# pilote_poele_2020-12-16_14-18-25.net
KiCad netlist of a schematic drawn in EasyEDA
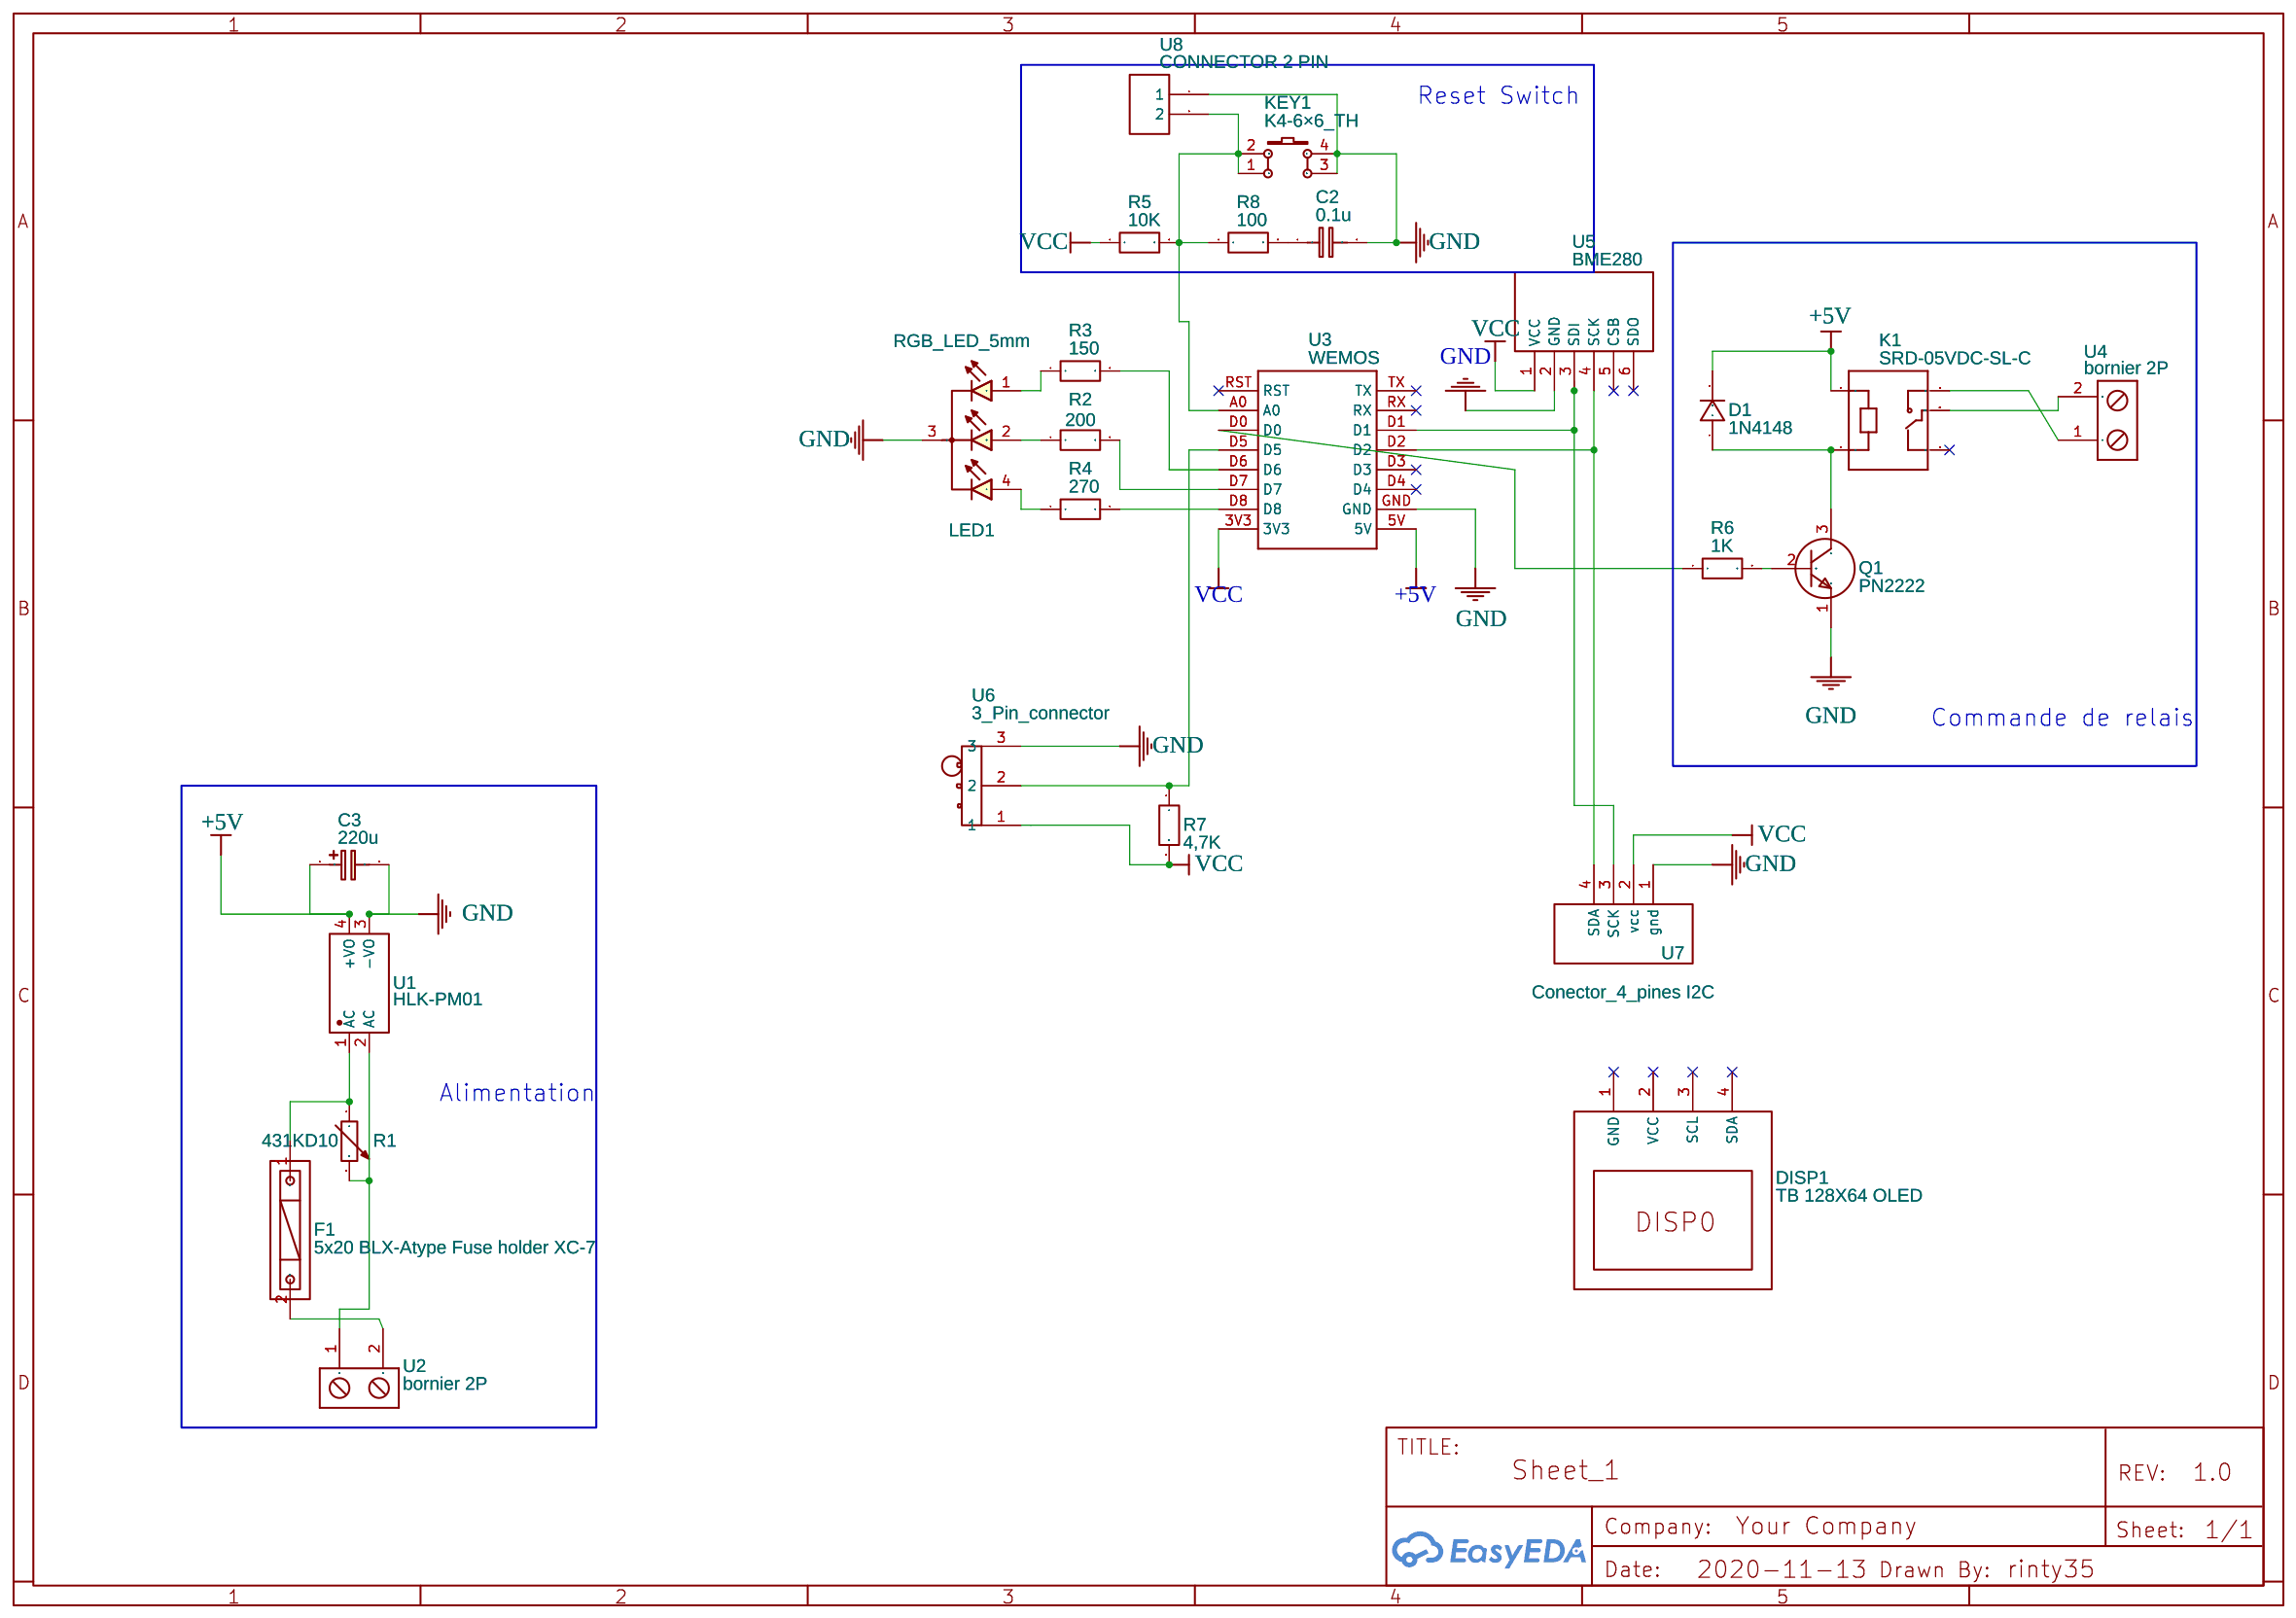
[diagram p0: schematic sheet]

(export (version "E")
  (design (tool "Eeschema 10.0.6"))
  (components
    (comp (ref "C2") (value "0.1u") (libsource (lib "") (part "C_0603_EU")))
    (comp (ref "C3") (value "220u") (libsource (lib "") (part "CE_TH_D4.0×F1.5_EU")))
    (comp (ref "D1")
      (value "1N4148")
      (fields (field (name "BOM_Supplier Part") "C14516"))
      (libsource (lib "") (part "1N4148"))
    )
    (comp (ref "DISP1") (value "TB 128X64 OLED") (libsource (lib "") (part "TB 128X64 OLED")))
    (comp (ref "F1")
      (value "5x20 BLX-Atype Fuse holder XC-7")
      (fields (field (name "BOM_Supplier Part") "C3131"))
      (libsource (lib "") (part "5x20 BLX-Atype Fuse holder XC-7"))
    )
    (comp (ref "K1") (value "SRD-05VDC-SL-C") (libsource (lib "") (part "SRD-05VDC-SL-C")))
    (comp (ref "KEY1")
      (value "K4-6×6_TH")
      (fields
        (field (name "BOM_Manufacturer Part") "K2-1102DP-E4SW-04")
        (field (name "BOM_Supplier Part") "C136684")
      )
      (libsource (lib "") (part "K4-6×6_TH"))
    )
    (comp (ref "LED1")
      (value "RGB_LED_5mm")
      (fields (field (name "BOM_Manufacturer Part") "φ5 RGB LED") (field (name "BOM_Supplier Part") "C32985"))
      (libsource (lib "") (part "RGB_LED_5mm"))
    )
    (comp (ref "Q1") (value "PN2222") (libsource (lib "") (part "PN2222")))
    (comp (ref "R1")
      (value "431KD10")
      (fields (field (name "BOM_Supplier Part") "C123332"))
      (libsource (lib "") (part "431KD10"))
    )
    (comp (ref "R2") (value "200") (libsource (lib "") (part "R_AXIAL-0.5_EU")))
    (comp (ref "R3") (value "150") (libsource (lib "") (part "R_AXIAL-0.5_EU")))
    (comp (ref "R4") (value "270") (libsource (lib "") (part "R_AXIAL-0.5_EU")))
    (comp (ref "R5") (value "10K") (libsource (lib "") (part "R_AXIAL-0.5_EU")))
    (comp (ref "R6") (value "1K") (libsource (lib "") (part "R_AXIAL-0.5_EU")))
    (comp (ref "R7") (value "4,7K") (libsource (lib "") (part "R_0603_EU")))
    (comp (ref "R8") (value "100") (libsource (lib "") (part "R_AXIAL-0.5_EU")))
    (comp (ref "U1")
      (value "HLK-PM01")
      (fields (field (name "BOM_Supplier Part") "C209903"))
      (libsource (lib "") (part "HLK-PM01"))
    )
    (comp (ref "U2")
      (value "bornier 2P")
      (fields (field (name "BOM_Manufacturer Part") "bornier"))
      (libsource (lib "") (part "bornier 2P_1"))
    )
    (comp (ref "U3") (value "WEMOS") (libsource (lib "") (part "WEMOS")))
    (comp (ref "U4")
      (value "bornier 2P")
      (fields (field (name "BOM_Manufacturer Part") "bornier"))
      (libsource (lib "") (part "bornier 2P"))
    )
    (comp (ref "U5") (value "BME280") (libsource (lib "") (part "BME280")))
    (comp (ref "U6")
      (value "3_Pin_connector")
      (fields (field (name "BOM_Manufacturer Part") "pin 3"))
      (libsource (lib "") (part "3_Pin_connector"))
    )
    (comp (ref "U7") (value "Conector_4_pines I2C") (libsource (lib "") (part "Conector_4_pines")))
    (comp (ref "U8") (value "CONNECTOR 2 PIN") (libsource (lib "") (part "CONNECTOR 2 PIN")))
  )
  (nets
    (net (code "1") (name "+5V") (class "Default")
      (node (ref "C3") (pin "1") (pinfunction "1_1") (pintype "unspecified"))
      (node (ref "D1") (pin "2") (pinfunction "2_2") (pintype "unspecified"))
      (node (ref "K1") (pin "A1") (pinfunction "A1_A1") (pintype "bidirectional"))
      (node (ref "U1") (pin "4") (pinfunction "+VO_4") (pintype "unspecified"))
      (node (ref "U3") (pin "5V") (pinfunction "5V_5V") (pintype "unspecified"))
    )
    (net (code "2") (name "GND") (class "Default")
      (node (ref "C2") (pin "2") (pinfunction "2_2") (pintype "unspecified"))
      (node (ref "C3") (pin "2") (pinfunction "2_2") (pintype "unspecified"))
      (node (ref "KEY1") (pin "3") (pinfunction "3_3") (pintype "unspecified"))
      (node (ref "KEY1") (pin "4") (pinfunction "4_4") (pintype "unspecified"))
      (node (ref "LED1") (pin "3") (pinfunction "3_3") (pintype "unspecified"))
      (node (ref "Q1") (pin "1") (pinfunction "E_1") (pintype "unspecified"))
      (node (ref "U1") (pin "3") (pinfunction "-VO_3") (pintype "unspecified"))
      (node (ref "U3") (pin "GND") (pinfunction "GND_GND") (pintype "unspecified"))
      (node (ref "U5") (pin "2") (pinfunction "GND_2") (pintype "unspecified"))
      (node (ref "U6") (pin "3") (pinfunction "3_3") (pintype "unspecified"))
      (node (ref "U7") (pin "1") (pinfunction "gnd_1") (pintype "unspecified"))
      (node (ref "U8") (pin "1") (pinfunction "1_1") (pintype "unspecified"))
    )
    (net (code "3") (name "Net-(C2-Pad1)") (class "Default")
      (node (ref "C2") (pin "1") (pinfunction "1_1") (pintype "unspecified"))
      (node (ref "R8") (pin "2") (pinfunction "2_2") (pintype "unspecified"))
    )
    (net (code "4") (name "Net-(F1-Pad1)") (class "Default")
      (node (ref "F1") (pin "1") (pinfunction "1_1") (pintype "unspecified"))
      (node (ref "R1") (pin "1") (pinfunction "1_1") (pintype "unspecified"))
      (node (ref "U1") (pin "1") (pinfunction "AC_1") (pintype "unspecified"))
    )
    (net (code "5") (name "Net-(F1-Pad2)") (class "Default")
      (node (ref "F1") (pin "2") (pinfunction "2_2") (pintype "unspecified"))
      (node (ref "U2") (pin "2") (pinfunction "2_2") (pintype "unspecified"))
    )
    (net (code "6") (name "Net-(K1-PadCOM)") (class "Default")
      (node (ref "K1") (pin "COM") (pinfunction "COM_COM") (pintype "bidirectional"))
      (node (ref "U4") (pin "2") (pinfunction "2_2") (pintype "unspecified"))
    )
    (net (code "7") (name "Net-(K1-PadNO)") (class "Default")
      (node (ref "K1") (pin "NO") (pinfunction "NO_NO") (pintype "bidirectional"))
      (node (ref "U4") (pin "1") (pinfunction "1_1") (pintype "unspecified"))
    )
    (net (code "8") (name "Net-(KEY1-Pad1)") (class "Default")
      (node (ref "KEY1") (pin "1") (pinfunction "1_1") (pintype "unspecified"))
      (node (ref "KEY1") (pin "2") (pinfunction "2_2") (pintype "unspecified"))
      (node (ref "R5") (pin "2") (pinfunction "2_2") (pintype "unspecified"))
      (node (ref "R8") (pin "1") (pinfunction "1_1") (pintype "unspecified"))
      (node (ref "U3") (pin "A0") (pinfunction "A0_A0") (pintype "unspecified"))
      (node (ref "U8") (pin "2") (pinfunction "2_2") (pintype "unspecified"))
    )
    (net (code "9") (name "Net-(LED1-Pad1)") (class "Default")
      (node (ref "LED1") (pin "1") (pinfunction "1_1") (pintype "unspecified"))
      (node (ref "R3") (pin "1") (pinfunction "1_1") (pintype "unspecified"))
    )
    (net (code "10") (name "Net-(LED1-Pad2)") (class "Default")
      (node (ref "LED1") (pin "2") (pinfunction "2_2") (pintype "unspecified"))
      (node (ref "R2") (pin "1") (pinfunction "1_1") (pintype "unspecified"))
    )
    (net (code "11") (name "Net-(LED1-Pad4)") (class "Default")
      (node (ref "LED1") (pin "4") (pinfunction "4_4") (pintype "unspecified"))
      (node (ref "R4") (pin "1") (pinfunction "1_1") (pintype "unspecified"))
    )
    (net (code "12") (name "Net-(Q1-B)") (class "Default")
      (node (ref "Q1") (pin "2") (pinfunction "B_2") (pintype "unspecified"))
      (node (ref "R6") (pin "2") (pinfunction "2_2") (pintype "unspecified"))
    )
    (net (code "13") (name "Net-(Q1-C)") (class "Default")
      (node (ref "D1") (pin "1") (pinfunction "1_1") (pintype "unspecified"))
      (node (ref "K1") (pin "A2") (pinfunction "A2_A2") (pintype "bidirectional"))
      (node (ref "Q1") (pin "3") (pinfunction "C_3") (pintype "unspecified"))
    )
    (net (code "14") (name "Net-(R1-Pad2)") (class "Default")
      (node (ref "R1") (pin "2") (pinfunction "2_2") (pintype "unspecified"))
      (node (ref "U1") (pin "2") (pinfunction "AC_2") (pintype "unspecified"))
      (node (ref "U2") (pin "1") (pinfunction "1_1") (pintype "unspecified"))
    )
    (net (code "15") (name "Net-(R2-Pad2)") (class "Default")
      (node (ref "R2") (pin "2") (pinfunction "2_2") (pintype "unspecified"))
      (node (ref "U3") (pin "D7") (pinfunction "D7_D7") (pintype "unspecified"))
    )
    (net (code "16") (name "Net-(R3-Pad2)") (class "Default")
      (node (ref "R3") (pin "2") (pinfunction "2_2") (pintype "unspecified"))
      (node (ref "U3") (pin "D6") (pinfunction "D6_D6") (pintype "unspecified"))
    )
    (net (code "17") (name "Net-(R4-Pad2)") (class "Default")
      (node (ref "R4") (pin "2") (pinfunction "2_2") (pintype "unspecified"))
      (node (ref "U3") (pin "D8") (pinfunction "D8_D8") (pintype "unspecified"))
    )
    (net (code "18") (name "Net-(R6-Pad1)") (class "Default")
      (node (ref "R6") (pin "1") (pinfunction "1_1") (pintype "unspecified"))
      (node (ref "U3") (pin "D0") (pinfunction "D0_D0") (pintype "unspecified"))
    )
    (net (code "19") (name "Net-(R7-Pad1)") (class "Default")
      (node (ref "R7") (pin "1") (pinfunction "1_1") (pintype "unspecified"))
      (node (ref "U3") (pin "D5") (pinfunction "D5_D5") (pintype "unspecified"))
      (node (ref "U6") (pin "2") (pinfunction "2_2") (pintype "unspecified"))
    )
    (net (code "20") (name "Net-(U5-SCK)") (class "Default")
      (node (ref "U3") (pin "D2") (pinfunction "D2_D2") (pintype "unspecified"))
      (node (ref "U5") (pin "4") (pinfunction "SCK_4") (pintype "unspecified"))
      (node (ref "U7") (pin "4") (pinfunction "SDA_4") (pintype "unspecified"))
    )
    (net (code "21") (name "Net-(U5-SDI)") (class "Default")
      (node (ref "U3") (pin "D1") (pinfunction "D1_D1") (pintype "unspecified"))
      (node (ref "U5") (pin "3") (pinfunction "SDI_3") (pintype "unspecified"))
      (node (ref "U7") (pin "3") (pinfunction "SCK_3") (pintype "unspecified"))
    )
    (net (code "22") (name "VCC") (class "Default")
      (node (ref "R5") (pin "1") (pinfunction "1_1") (pintype "unspecified"))
      (node (ref "R7") (pin "2") (pinfunction "2_2") (pintype "unspecified"))
      (node (ref "U3") (pin "3V3") (pinfunction "3V3_3V3") (pintype "unspecified"))
      (node (ref "U5") (pin "1") (pinfunction "VCC_1") (pintype "unspecified"))
      (node (ref "U6") (pin "1") (pinfunction "1_1") (pintype "unspecified"))
      (node (ref "U7") (pin "2") (pinfunction "vcc_2") (pintype "unspecified"))
    )
    (net (code "23") (name "unconnected-(DISP1-GND-Pad1)") (class "Default")
      (node (ref "DISP1") (pin "1") (pinfunction "GND_1") (pintype "unspecified+no_connect"))
    )
    (net (code "24") (name "unconnected-(DISP1-SCL-Pad3)") (class "Default")
      (node (ref "DISP1") (pin "3") (pinfunction "SCL_3") (pintype "unspecified+no_connect"))
    )
    (net (code "25") (name "unconnected-(DISP1-SDA-Pad4)") (class "Default")
      (node (ref "DISP1") (pin "4") (pinfunction "SDA_4") (pintype "unspecified+no_connect"))
    )
    (net (code "26") (name "unconnected-(DISP1-VCC-Pad2)") (class "Default")
      (node (ref "DISP1") (pin "2") (pinfunction "VCC_2") (pintype "unspecified+no_connect"))
    )
    (net (code "27") (name "unconnected-(K1-PadNC)") (class "Default")
      (node (ref "K1") (pin "NC") (pinfunction "NC_NC") (pintype "bidirectional+no_connect"))
    )
    (net (code "28") (name "unconnected-(U3-PadD3)") (class "Default")
      (node (ref "U3") (pin "D3") (pinfunction "D3_D3") (pintype "unspecified+no_connect"))
    )
    (net (code "29") (name "unconnected-(U3-PadD4)") (class "Default")
      (node (ref "U3") (pin "D4") (pinfunction "D4_D4") (pintype "unspecified+no_connect"))
    )
    (net (code "30") (name "unconnected-(U3-PadRST)") (class "Default")
      (node (ref "U3") (pin "RST") (pinfunction "RST_RST") (pintype "unspecified+no_connect"))
    )
    (net (code "31") (name "unconnected-(U3-PadRX)") (class "Default")
      (node (ref "U3") (pin "RX") (pinfunction "RX_RX") (pintype "unspecified+no_connect"))
    )
    (net (code "32") (name "unconnected-(U3-PadTX)") (class "Default")
      (node (ref "U3") (pin "TX") (pinfunction "TX_TX") (pintype "unspecified+no_connect"))
    )
    (net (code "33") (name "unconnected-(U5-CSB-Pad5)") (class "Default")
      (node (ref "U5") (pin "5") (pinfunction "CSB_5") (pintype "unspecified+no_connect"))
    )
    (net (code "34") (name "unconnected-(U5-SDO-Pad6)") (class "Default")
      (node (ref "U5") (pin "6") (pinfunction "SDO_6") (pintype "unspecified+no_connect"))
    )
  )
)
